# 02_LCD.net
KiCad netlist of a schematic drawn in Altium Designer
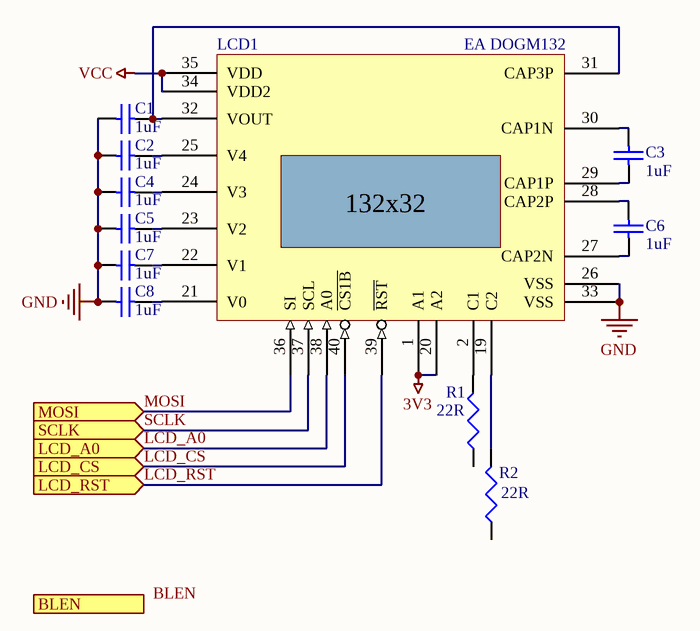
[diagram p0: [02] LCD.SchDoc]

(export (version "E")
  (design (tool "Eeschema 10.0.6"))
  (components
    (comp (ref "C1")
      (value "1uF")
      (footprint "1608[0603]")
      (description "Capacitor (Semiconductor SIM Model)")
      (fields (field (name "Comment") "Cap Semi") (field (name "PUBLISHER") "Altium Limited"))
      (libsource (lib "Miscellaneous Devices") (part "Cap Semi"))
    )
    (comp (ref "C2")
      (value "1uF")
      (footprint "1608[0603]")
      (description "Capacitor (Semiconductor SIM Model)")
      (fields (field (name "Comment") "Cap Semi") (field (name "PUBLISHER") "Altium Limited"))
      (libsource (lib "Miscellaneous Devices") (part "Cap Semi"))
    )
    (comp (ref "C3")
      (value "1uF")
      (footprint "1608[0603]")
      (description "Capacitor (Semiconductor SIM Model)")
      (fields (field (name "Comment") "Cap Semi") (field (name "PUBLISHER") "Altium Limited"))
      (libsource (lib "Miscellaneous Devices") (part "Cap Semi"))
    )
    (comp (ref "C4")
      (value "1uF")
      (footprint "1608[0603]")
      (description "Capacitor (Semiconductor SIM Model)")
      (fields (field (name "Comment") "Cap Semi") (field (name "PUBLISHER") "Altium Limited"))
      (libsource (lib "Miscellaneous Devices") (part "Cap Semi"))
    )
    (comp (ref "C5")
      (value "1uF")
      (footprint "1608[0603]")
      (description "Capacitor (Semiconductor SIM Model)")
      (fields (field (name "Comment") "Cap Semi") (field (name "PUBLISHER") "Altium Limited"))
      (libsource (lib "Miscellaneous Devices") (part "Cap Semi"))
    )
    (comp (ref "C6")
      (value "1uF")
      (footprint "1608[0603]")
      (description "Capacitor (Semiconductor SIM Model)")
      (fields (field (name "Comment") "Cap Semi") (field (name "PUBLISHER") "Altium Limited"))
      (libsource (lib "Miscellaneous Devices") (part "Cap Semi"))
    )
    (comp (ref "C7")
      (value "1uF")
      (footprint "1608[0603]")
      (description "Capacitor (Semiconductor SIM Model)")
      (fields (field (name "Comment") "Cap Semi") (field (name "PUBLISHER") "Altium Limited"))
      (libsource (lib "Miscellaneous Devices") (part "Cap Semi"))
    )
    (comp (ref "C8")
      (value "1uF")
      (footprint "1608[0603]")
      (description "Capacitor (Semiconductor SIM Model)")
      (fields (field (name "Comment") "Cap Semi") (field (name "PUBLISHER") "Altium Limited"))
      (libsource (lib "Miscellaneous Devices") (part "Cap Semi"))
    )
    (comp (ref "LCD1")
      (value "EA DOGM132")
      (footprint "EA DOGM132-5")
      (description "132x32 graphical LCD")
      (libsource (lib "6DOF IMU_ver1") (part "EA DOGM132"))
    )
    (comp (ref "R1")
      (value "22R")
      (footprint "J1-0603")
      (description "Resistor")
      (fields (field (name "Comment") "Res3") (field (name "PUBLISHER") "Altium Limited"))
      (libsource (lib "Miscellaneous Devices") (part "Res3"))
    )
    (comp (ref "R2")
      (value "22R")
      (footprint "J1-0603")
      (description "Resistor")
      (fields (field (name "Comment") "Res3") (field (name "PUBLISHER") "Altium Limited"))
      (libsource (lib "Miscellaneous Devices") (part "Res3"))
    )
  )
  (nets
    (net (code "2") (name "/LCD_A0") (class "Default")
      (node (ref "LCD1") (pin "38") (pinfunction "A0_38") (pintype "input"))
    )
    (net (code "3") (name "/LCD_CS") (class "Default")
      (node (ref "LCD1") (pin "40") (pinfunction "~{CS1B}_40") (pintype "input"))
    )
    (net (code "4") (name "/LCD_RST") (class "Default")
      (node (ref "LCD1") (pin "39") (pinfunction "~{RST}_39") (pintype "input"))
    )
    (net (code "5") (name "/MOSI") (class "Default")
      (node (ref "LCD1") (pin "36") (pinfunction "SI_36") (pintype "input"))
    )
    (net (code "6") (name "/SCLK") (class "Default")
      (node (ref "LCD1") (pin "37") (pinfunction "SCL_37") (pintype "input"))
    )
    (net (code "7") (name "3V3") (class "Default")
      (node (ref "LCD1") (pin "1") (pinfunction "A1_1") (pintype "passive"))
      (node (ref "LCD1") (pin "20") (pinfunction "A2_20") (pintype "passive"))
    )
    (net (code "8") (name "GND") (class "Default")
      (node (ref "C1") (pin "1") (pinfunction "1_1") (pintype "passive"))
      (node (ref "C2") (pin "1") (pinfunction "1_1") (pintype "passive"))
      (node (ref "C4") (pin "1") (pinfunction "1_1") (pintype "passive"))
      (node (ref "C5") (pin "1") (pinfunction "1_1") (pintype "passive"))
      (node (ref "C7") (pin "1") (pinfunction "1_1") (pintype "passive"))
      (node (ref "C8") (pin "1") (pinfunction "1_1") (pintype "passive"))
      (node (ref "LCD1") (pin "26") (pinfunction "VSS_26") (pintype "passive"))
      (node (ref "LCD1") (pin "33") (pinfunction "VSS_33") (pintype "passive"))
    )
    (net (code "9") (name "Net-(LCD1-C1)") (class "Default")
      (node (ref "LCD1") (pin "2") (pinfunction "C1_2") (pintype "passive"))
      (node (ref "R1") (pin "2") (pinfunction "2_2") (pintype "passive"))
    )
    (net (code "10") (name "Net-(LCD1-C2)") (class "Default")
      (node (ref "LCD1") (pin "19") (pinfunction "C2_19") (pintype "passive"))
      (node (ref "R2") (pin "2") (pinfunction "2_2") (pintype "passive"))
    )
    (net (code "11") (name "Net-(LCD1-CAP1N)") (class "Default")
      (node (ref "C3") (pin "1") (pinfunction "1_1") (pintype "passive"))
      (node (ref "LCD1") (pin "30") (pinfunction "CAP1N_30") (pintype "passive"))
    )
    (net (code "12") (name "Net-(LCD1-CAP1P)") (class "Default")
      (node (ref "C3") (pin "2") (pinfunction "2_2") (pintype "passive"))
      (node (ref "LCD1") (pin "29") (pinfunction "CAP1P_29") (pintype "passive"))
    )
    (net (code "13") (name "Net-(LCD1-CAP2N)") (class "Default")
      (node (ref "C6") (pin "2") (pinfunction "2_2") (pintype "passive"))
      (node (ref "LCD1") (pin "27") (pinfunction "CAP2N_27") (pintype "passive"))
    )
    (net (code "14") (name "Net-(LCD1-CAP2P)") (class "Default")
      (node (ref "C6") (pin "1") (pinfunction "1_1") (pintype "passive"))
      (node (ref "LCD1") (pin "28") (pinfunction "CAP2P_28") (pintype "passive"))
    )
    (net (code "15") (name "Net-(LCD1-CAP3P)") (class "Default")
      (node (ref "C1") (pin "2") (pinfunction "2_2") (pintype "passive"))
      (node (ref "LCD1") (pin "31") (pinfunction "CAP3P_31") (pintype "passive"))
      (node (ref "LCD1") (pin "32") (pinfunction "VOUT_32") (pintype "passive"))
    )
    (net (code "16") (name "Net-(LCD1-V0)") (class "Default")
      (node (ref "C8") (pin "2") (pinfunction "2_2") (pintype "passive"))
      (node (ref "LCD1") (pin "21") (pinfunction "V0_21") (pintype "passive"))
    )
    (net (code "17") (name "Net-(LCD1-V1)") (class "Default")
      (node (ref "C7") (pin "2") (pinfunction "2_2") (pintype "passive"))
      (node (ref "LCD1") (pin "22") (pinfunction "V1_22") (pintype "passive"))
    )
    (net (code "18") (name "Net-(LCD1-V2)") (class "Default")
      (node (ref "C5") (pin "2") (pinfunction "2_2") (pintype "passive"))
      (node (ref "LCD1") (pin "23") (pinfunction "V2_23") (pintype "passive"))
    )
    (net (code "19") (name "Net-(LCD1-V3)") (class "Default")
      (node (ref "C4") (pin "2") (pinfunction "2_2") (pintype "passive"))
      (node (ref "LCD1") (pin "24") (pinfunction "V3_24") (pintype "passive"))
    )
    (net (code "20") (name "Net-(LCD1-V4)") (class "Default")
      (node (ref "C2") (pin "2") (pinfunction "2_2") (pintype "passive"))
      (node (ref "LCD1") (pin "25") (pinfunction "V4_25") (pintype "passive"))
    )
    (net (code "21") (name "VCC") (class "Default")
      (node (ref "LCD1") (pin "34") (pinfunction "VDD2_34") (pintype "passive"))
      (node (ref "LCD1") (pin "35") (pinfunction "VDD_35") (pintype "passive"))
    )
    (net (code "22") (name "unconnected-(R1-Pad1)") (class "Default")
      (node (ref "R1") (pin "1") (pinfunction "1_1") (pintype "passive"))
    )
    (net (code "23") (name "unconnected-(R2-Pad1)") (class "Default")
      (node (ref "R2") (pin "1") (pinfunction "1_1") (pintype "passive"))
    )
  )
)
